# typewriter_shift.net
KiCad netlist of a schematic drawn in EAGLE
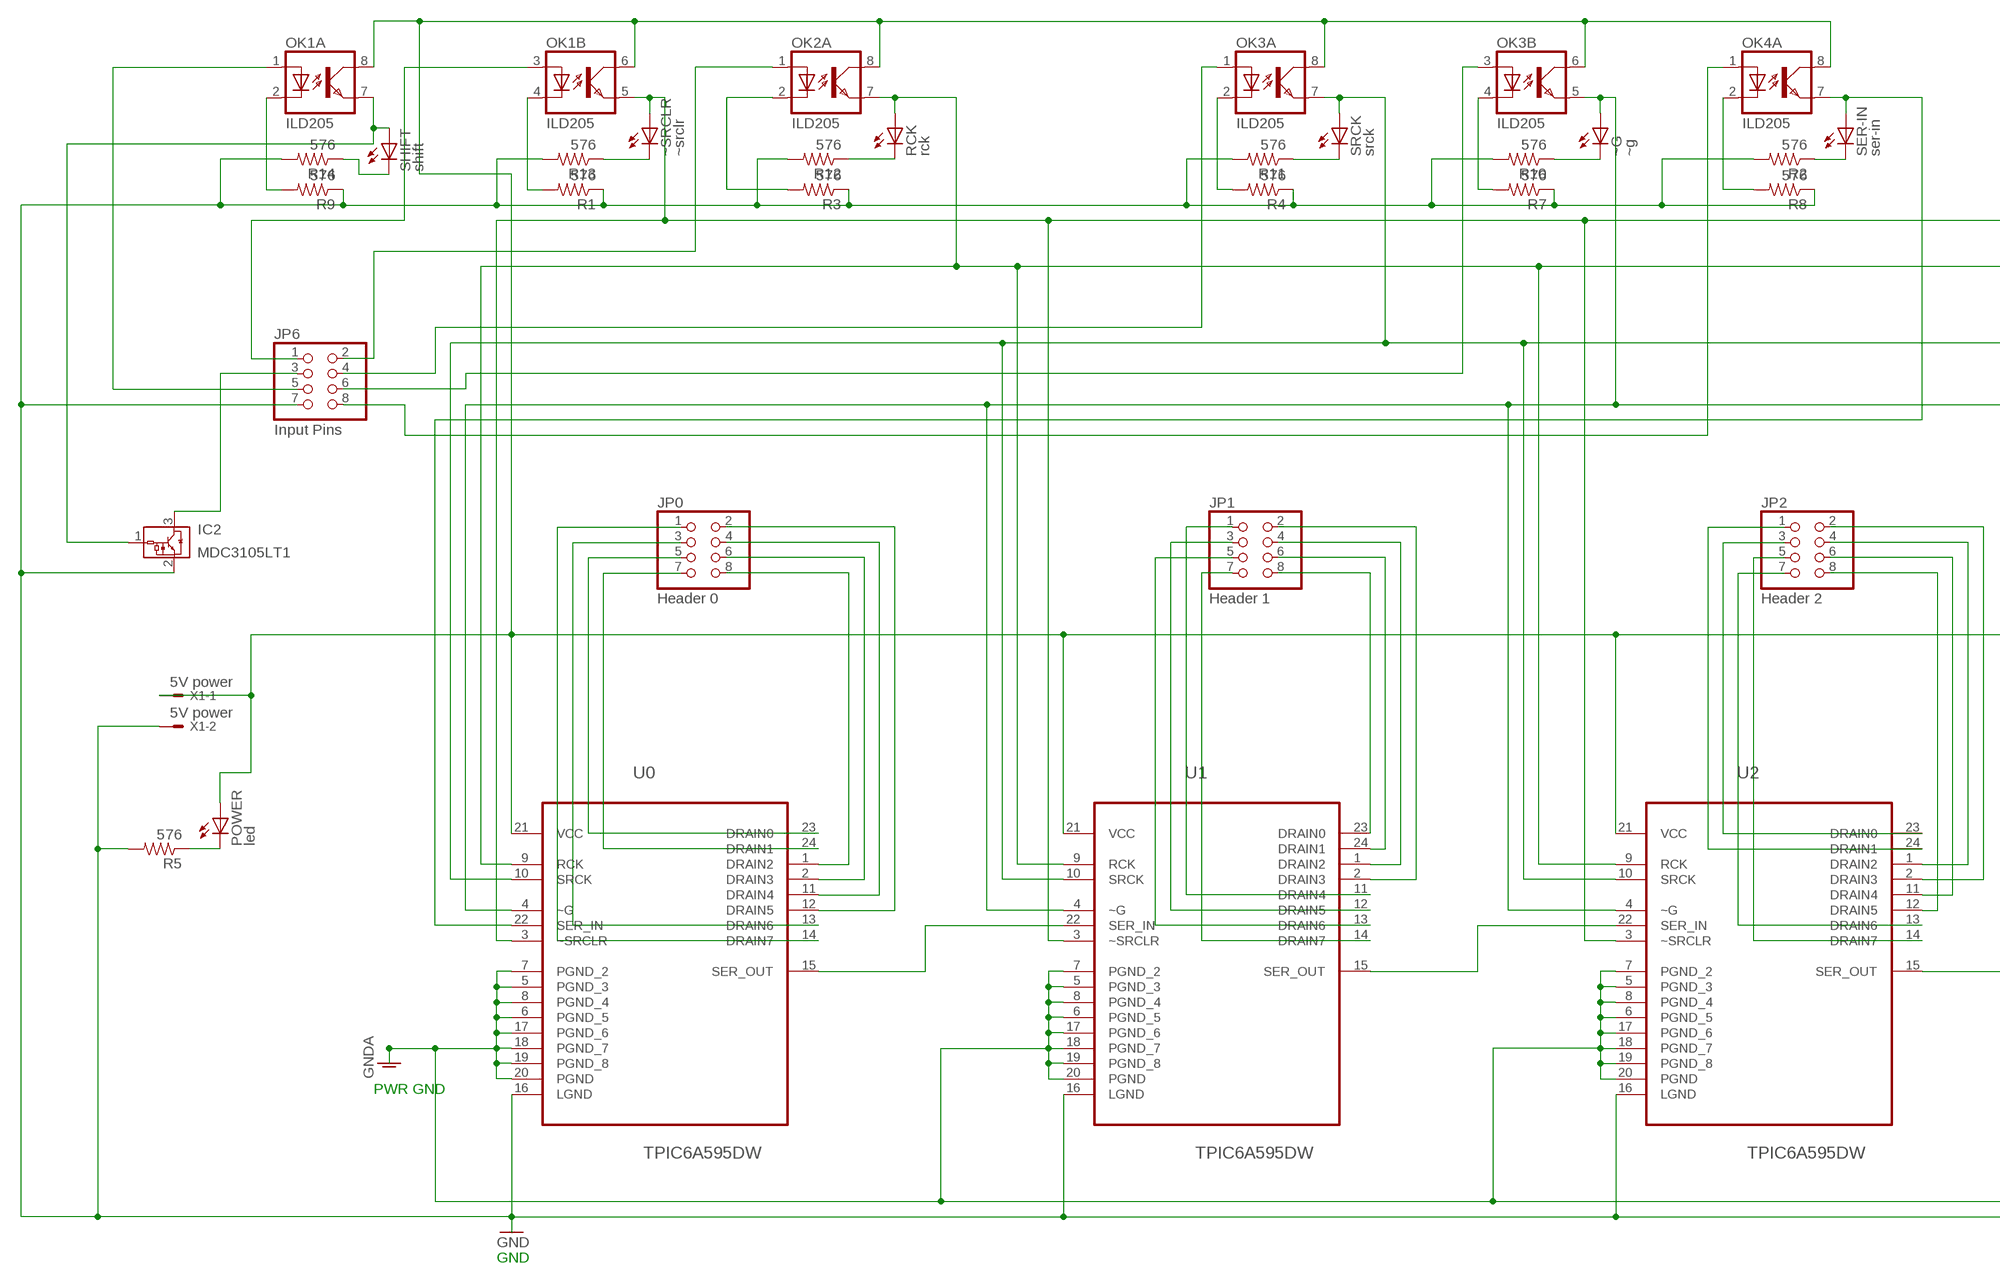
[diagram p0: schematic, sheet 1, part 1 of 2]
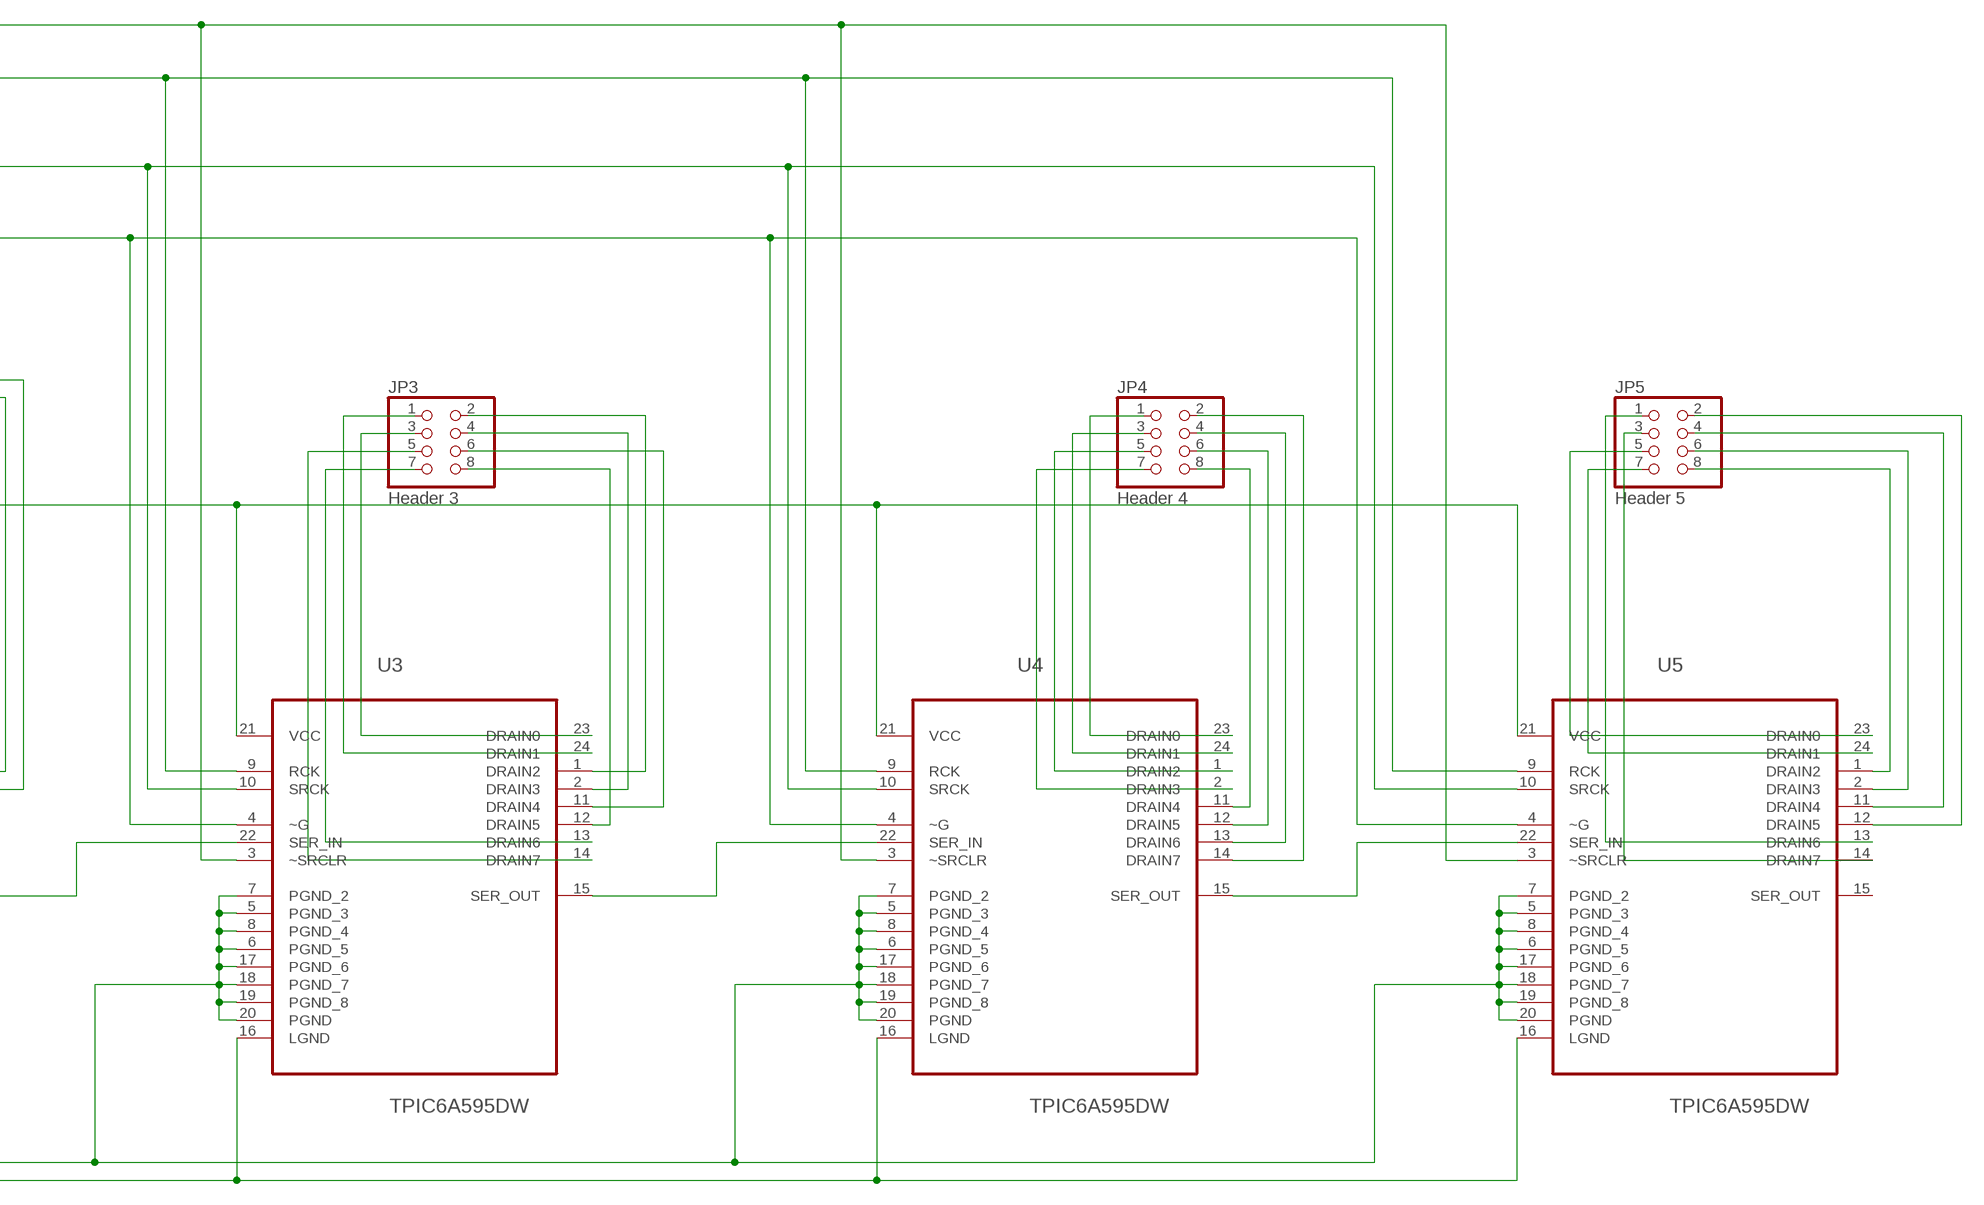
[diagram p1: schematic, sheet 1, part 2 of 2]

(export (version "E")
  (design (tool "Eeschema 10.0.6"))
  (components
    (comp (ref "IC2")
      (value "MDC3105LT1")
      (footprint "eagle-import:SOT23")
      (fields (field (name "MF") "ON SEMICONDUCTOR"))
      (libsource (lib "eagle-import") (part "MDC3105LT1"))
    )
    (comp (ref "JP0")
      (value "Header 0")
      (footprint "eagle-import:2X04_90")
      (libsource (lib "eagle-import") (part "PINHD-2X4/90"))
    )
    (comp (ref "JP1")
      (value "Header 1")
      (footprint "eagle-import:2X04_90")
      (libsource (lib "eagle-import") (part "PINHD-2X4/90"))
    )
    (comp (ref "JP2")
      (value "Header 2")
      (footprint "eagle-import:2X04_90")
      (libsource (lib "eagle-import") (part "PINHD-2X4/90"))
    )
    (comp (ref "JP3")
      (value "Header 3")
      (footprint "eagle-import:2X04_90")
      (libsource (lib "eagle-import") (part "PINHD-2X4/90"))
    )
    (comp (ref "JP4")
      (value "Header 4")
      (footprint "eagle-import:2X04_90")
      (libsource (lib "eagle-import") (part "PINHD-2X4/90"))
    )
    (comp (ref "JP5")
      (value "Header 5")
      (footprint "eagle-import:2X04_90")
      (libsource (lib "eagle-import") (part "PINHD-2X4/90"))
    )
    (comp (ref "JP6")
      (value "Input Pins")
      (footprint "eagle-import:2X04_90")
      (libsource (lib "eagle-import") (part "PINHD-2X4/90"))
    )
    (comp (ref "OK1")
      (value "ILD205")
      (footprint "eagle-import:SOIC08")
      (fields (field (name "MF") "VISHAY/TELEFUNKEN") (field (name "MPN") "ILD205T"))
      (libsource (lib "eagle-import") (part "ILD205"))
    )
    (comp (ref "OK2")
      (value "ILD205")
      (footprint "eagle-import:SOIC08")
      (fields (field (name "MF") "VISHAY/TELEFUNKEN") (field (name "MPN") "ILD205T"))
      (libsource (lib "eagle-import") (part "ILD205"))
    )
    (comp (ref "OK3")
      (value "ILD205")
      (footprint "eagle-import:SOIC08")
      (fields (field (name "MF") "VISHAY/TELEFUNKEN") (field (name "MPN") "ILD205T"))
      (libsource (lib "eagle-import") (part "ILD205"))
    )
    (comp (ref "OK4")
      (value "ILD205")
      (footprint "eagle-import:SOIC08")
      (fields (field (name "MF") "VISHAY/TELEFUNKEN") (field (name "MPN") "ILD205T"))
      (libsource (lib "eagle-import") (part "ILD205"))
    )
    (comp (ref "POWER")
      (value "led")
      (footprint "eagle-import:SML1206")
      (libsource (lib "eagle-import") (part "LEDSML1206"))
    )
    (comp (ref "R1")
      (value "576")
      (footprint "eagle-import:R2512")
      (libsource (lib "eagle-import") (part "R-US_R2512"))
    )
    (comp (ref "R2")
      (value "576")
      (footprint "eagle-import:R2512")
      (libsource (lib "eagle-import") (part "R-US_R2512"))
    )
    (comp (ref "R3")
      (value "576")
      (footprint "eagle-import:R2512")
      (libsource (lib "eagle-import") (part "R-US_R2512"))
    )
    (comp (ref "R4")
      (value "576")
      (footprint "eagle-import:R2512")
      (libsource (lib "eagle-import") (part "R-US_R2512"))
    )
    (comp (ref "R5")
      (value "576")
      (footprint "eagle-import:R2512")
      (libsource (lib "eagle-import") (part "R-US_R2512"))
    )
    (comp (ref "R7")
      (value "576")
      (footprint "eagle-import:R2512")
      (libsource (lib "eagle-import") (part "R-US_R2512"))
    )
    (comp (ref "R8")
      (value "576")
      (footprint "eagle-import:R2512")
      (libsource (lib "eagle-import") (part "R-US_R2512"))
    )
    (comp (ref "R9")
      (value "576")
      (footprint "eagle-import:R2512")
      (libsource (lib "eagle-import") (part "R-US_R2512"))
    )
    (comp (ref "R10")
      (value "576")
      (footprint "eagle-import:R2512")
      (libsource (lib "eagle-import") (part "R-US_R2512"))
    )
    (comp (ref "R11")
      (value "576")
      (footprint "eagle-import:R2512")
      (libsource (lib "eagle-import") (part "R-US_R2512"))
    )
    (comp (ref "R12")
      (value "576")
      (footprint "eagle-import:R2512")
      (libsource (lib "eagle-import") (part "R-US_R2512"))
    )
    (comp (ref "R13")
      (value "576")
      (footprint "eagle-import:R2512")
      (libsource (lib "eagle-import") (part "R-US_R2512"))
    )
    (comp (ref "R14")
      (value "576")
      (footprint "eagle-import:R2512")
      (libsource (lib "eagle-import") (part "R-US_R2512"))
    )
    (comp (ref "RCK")
      (value "rck")
      (footprint "eagle-import:SML1206")
      (libsource (lib "eagle-import") (part "LEDSML1206"))
    )
    (comp (ref "SER-IN")
      (value "ser-in")
      (footprint "eagle-import:SML1206")
      (libsource (lib "eagle-import") (part "LEDSML1206"))
    )
    (comp (ref "SHIFT")
      (value "shift")
      (footprint "eagle-import:SML1206")
      (libsource (lib "eagle-import") (part "LEDSML1206"))
    )
    (comp (ref "SRCK")
      (value "srck")
      (footprint "eagle-import:SML1206")
      (libsource (lib "eagle-import") (part "LEDSML1206"))
    )
    (comp (ref "U0")
      (value "TPIC6A595DW")
      (footprint "eagle-import:SOIC127P1030X265-24N")
      (libsource (lib "eagle-import") (part "TPIC6A595DW"))
    )
    (comp (ref "U1")
      (value "TPIC6A595DW")
      (footprint "eagle-import:SOIC127P1030X265-24N")
      (libsource (lib "eagle-import") (part "TPIC6A595DW"))
    )
    (comp (ref "U2")
      (value "TPIC6A595DW")
      (footprint "eagle-import:SOIC127P1030X265-24N")
      (libsource (lib "eagle-import") (part "TPIC6A595DW"))
    )
    (comp (ref "U3")
      (value "TPIC6A595DW")
      (footprint "eagle-import:SOIC127P1030X265-24N")
      (libsource (lib "eagle-import") (part "TPIC6A595DW"))
    )
    (comp (ref "U4")
      (value "TPIC6A595DW")
      (footprint "eagle-import:SOIC127P1030X265-24N")
      (libsource (lib "eagle-import") (part "TPIC6A595DW"))
    )
    (comp (ref "U5")
      (value "TPIC6A595DW")
      (footprint "eagle-import:SOIC127P1030X265-24N")
      (libsource (lib "eagle-import") (part "TPIC6A595DW"))
    )
    (comp (ref "X1")
      (value "5V power")
      (footprint "eagle-import:KK-156-2")
      (libsource (lib "eagle-import") (part "KK-156-2"))
    )
    (comp (ref "~G")
      (value "~g")
      (footprint "eagle-import:SML1206")
      (libsource (lib "eagle-import") (part "LEDSML1206"))
    )
    (comp (ref "~SRCLR")
      (value "~srclr")
      (footprint "eagle-import:SML1206")
      (libsource (lib "eagle-import") (part "LEDSML1206"))
    )
  )
  (nets
    (net (code "1") (name "GND") (class "Default")
      (node (ref "IC2") (pin "2") (pinfunction "GND_2") (pintype "passive"))
      (node (ref "JP6") (pin "7") (pinfunction "7_7") (pintype "passive"))
      (node (ref "R1") (pin "1") (pinfunction "1_1") (pintype "passive"))
      (node (ref "R10") (pin "2") (pinfunction "2_2") (pintype "passive"))
      (node (ref "R11") (pin "2") (pinfunction "2_2") (pintype "passive"))
      (node (ref "R12") (pin "2") (pinfunction "2_2") (pintype "passive"))
      (node (ref "R13") (pin "2") (pinfunction "2_2") (pintype "passive"))
      (node (ref "R14") (pin "2") (pinfunction "2_2") (pintype "passive"))
      (node (ref "R2") (pin "2") (pinfunction "2_2") (pintype "passive"))
      (node (ref "R3") (pin "1") (pinfunction "1_1") (pintype "passive"))
      (node (ref "R4") (pin "1") (pinfunction "1_1") (pintype "passive"))
      (node (ref "R5") (pin "2") (pinfunction "2_2") (pintype "passive"))
      (node (ref "R7") (pin "1") (pinfunction "1_1") (pintype "passive"))
      (node (ref "R8") (pin "1") (pinfunction "1_1") (pintype "passive"))
      (node (ref "R9") (pin "1") (pinfunction "1_1") (pintype "passive"))
      (node (ref "U0") (pin "16") (pinfunction "LGND_16") (pintype "passive"))
      (node (ref "U1") (pin "16") (pinfunction "LGND_16") (pintype "passive"))
      (node (ref "U2") (pin "16") (pinfunction "LGND_16") (pintype "passive"))
      (node (ref "U3") (pin "16") (pinfunction "LGND_16") (pintype "passive"))
      (node (ref "U4") (pin "16") (pinfunction "LGND_16") (pintype "passive"))
      (node (ref "U5") (pin "16") (pinfunction "LGND_16") (pintype "passive"))
      (node (ref "X1") (pin "2") (pinfunction "S_2") (pintype "passive"))
    )
    (net (code "2") (name "GNDA") (class "Default")
      (node (ref "U0") (pin "17") (pinfunction "PGND_6_17") (pintype "passive"))
      (node (ref "U0") (pin "18") (pinfunction "PGND_7_18") (pintype "passive"))
      (node (ref "U0") (pin "19") (pinfunction "PGND_8_19") (pintype "passive"))
      (node (ref "U0") (pin "20") (pinfunction "PGND_20") (pintype "passive"))
      (node (ref "U0") (pin "5") (pinfunction "PGND_3_5") (pintype "passive"))
      (node (ref "U0") (pin "6") (pinfunction "PGND_5_6") (pintype "passive"))
      (node (ref "U0") (pin "7") (pinfunction "PGND_2_7") (pintype "passive"))
      (node (ref "U0") (pin "8") (pinfunction "PGND_4_8") (pintype "passive"))
      (node (ref "U1") (pin "17") (pinfunction "PGND_6_17") (pintype "passive"))
      (node (ref "U1") (pin "18") (pinfunction "PGND_7_18") (pintype "passive"))
      (node (ref "U1") (pin "19") (pinfunction "PGND_8_19") (pintype "passive"))
      (node (ref "U1") (pin "20") (pinfunction "PGND_20") (pintype "passive"))
      (node (ref "U1") (pin "5") (pinfunction "PGND_3_5") (pintype "passive"))
      (node (ref "U1") (pin "6") (pinfunction "PGND_5_6") (pintype "passive"))
      (node (ref "U1") (pin "7") (pinfunction "PGND_2_7") (pintype "passive"))
      (node (ref "U1") (pin "8") (pinfunction "PGND_4_8") (pintype "passive"))
      (node (ref "U2") (pin "17") (pinfunction "PGND_6_17") (pintype "passive"))
      (node (ref "U2") (pin "18") (pinfunction "PGND_7_18") (pintype "passive"))
      (node (ref "U2") (pin "19") (pinfunction "PGND_8_19") (pintype "passive"))
      (node (ref "U2") (pin "20") (pinfunction "PGND_20") (pintype "passive"))
      (node (ref "U2") (pin "5") (pinfunction "PGND_3_5") (pintype "passive"))
      (node (ref "U2") (pin "6") (pinfunction "PGND_5_6") (pintype "passive"))
      (node (ref "U2") (pin "7") (pinfunction "PGND_2_7") (pintype "passive"))
      (node (ref "U2") (pin "8") (pinfunction "PGND_4_8") (pintype "passive"))
      (node (ref "U3") (pin "17") (pinfunction "PGND_6_17") (pintype "passive"))
      (node (ref "U3") (pin "18") (pinfunction "PGND_7_18") (pintype "passive"))
      (node (ref "U3") (pin "19") (pinfunction "PGND_8_19") (pintype "passive"))
      (node (ref "U3") (pin "20") (pinfunction "PGND_20") (pintype "passive"))
      (node (ref "U3") (pin "5") (pinfunction "PGND_3_5") (pintype "passive"))
      (node (ref "U3") (pin "6") (pinfunction "PGND_5_6") (pintype "passive"))
      (node (ref "U3") (pin "7") (pinfunction "PGND_2_7") (pintype "passive"))
      (node (ref "U3") (pin "8") (pinfunction "PGND_4_8") (pintype "passive"))
      (node (ref "U4") (pin "17") (pinfunction "PGND_6_17") (pintype "passive"))
      (node (ref "U4") (pin "18") (pinfunction "PGND_7_18") (pintype "passive"))
      (node (ref "U4") (pin "19") (pinfunction "PGND_8_19") (pintype "passive"))
      (node (ref "U4") (pin "20") (pinfunction "PGND_20") (pintype "passive"))
      (node (ref "U4") (pin "5") (pinfunction "PGND_3_5") (pintype "passive"))
      (node (ref "U4") (pin "6") (pinfunction "PGND_5_6") (pintype "passive"))
      (node (ref "U4") (pin "7") (pinfunction "PGND_2_7") (pintype "passive"))
      (node (ref "U4") (pin "8") (pinfunction "PGND_4_8") (pintype "passive"))
      (node (ref "U5") (pin "17") (pinfunction "PGND_6_17") (pintype "passive"))
      (node (ref "U5") (pin "18") (pinfunction "PGND_7_18") (pintype "passive"))
      (node (ref "U5") (pin "19") (pinfunction "PGND_8_19") (pintype "passive"))
      (node (ref "U5") (pin "20") (pinfunction "PGND_20") (pintype "passive"))
      (node (ref "U5") (pin "5") (pinfunction "PGND_3_5") (pintype "passive"))
      (node (ref "U5") (pin "6") (pinfunction "PGND_5_6") (pintype "passive"))
      (node (ref "U5") (pin "7") (pinfunction "PGND_2_7") (pintype "passive"))
      (node (ref "U5") (pin "8") (pinfunction "PGND_4_8") (pintype "passive"))
    )
    (net (code "3") (name "Net-(IC2-VIN)") (class "Default")
      (node (ref "IC2") (pin "1") (pinfunction "VIN_1") (pintype "passive"))
      (node (ref "OK1") (pin "7") (pinfunction "EMIT_7") (pintype "passive"))
      (node (ref "SHIFT") (pin "A") (pinfunction "A_A") (pintype "passive"))
    )
    (net (code "4") (name "Net-(IC2-VOUT)") (class "Default")
      (node (ref "IC2") (pin "3") (pinfunction "VOUT_3") (pintype "passive"))
      (node (ref "JP6") (pin "3") (pinfunction "3_3") (pintype "passive"))
    )
    (net (code "5") (name "Net-(OK1A-A)") (class "Default")
      (node (ref "JP6") (pin "5") (pinfunction "5_5") (pintype "passive"))
      (node (ref "OK1") (pin "1") (pinfunction "A_1") (pintype "passive"))
    )
    (net (code "6") (name "Net-(OK1A-C)") (class "Default")
      (node (ref "OK1") (pin "2") (pinfunction "C_2") (pintype "passive"))
      (node (ref "R9") (pin "2") (pinfunction "2_2") (pintype "passive"))
    )
    (net (code "7") (name "Net-(OK1A-COL)") (class "Default")
      (node (ref "OK1") (pin "6") (pinfunction "COL_6") (pintype "passive"))
      (node (ref "OK1") (pin "8") (pinfunction "COL_8") (pintype "passive"))
      (node (ref "OK2") (pin "8") (pinfunction "COL_8") (pintype "passive"))
      (node (ref "OK3") (pin "6") (pinfunction "COL_6") (pintype "passive"))
      (node (ref "OK3") (pin "8") (pinfunction "COL_8") (pintype "passive"))
      (node (ref "OK4") (pin "8") (pinfunction "COL_8") (pintype "passive"))
      (node (ref "POWER") (pin "A") (pinfunction "A_A") (pintype "passive"))
      (node (ref "U0") (pin "21") (pinfunction "VCC_21") (pintype "power_in"))
      (node (ref "U1") (pin "21") (pinfunction "VCC_21") (pintype "power_in"))
      (node (ref "U2") (pin "21") (pinfunction "VCC_21") (pintype "power_in"))
      (node (ref "U3") (pin "21") (pinfunction "VCC_21") (pintype "power_in"))
      (node (ref "U4") (pin "21") (pinfunction "VCC_21") (pintype "power_in"))
      (node (ref "U5") (pin "21") (pinfunction "VCC_21") (pintype "power_in"))
      (node (ref "X1") (pin "1") (pinfunction "S_1") (pintype "passive"))
    )
    (net (code "8") (name "Net-(OK1B-A)") (class "Default")
      (node (ref "JP6") (pin "1") (pinfunction "1_1") (pintype "passive"))
      (node (ref "OK1") (pin "3") (pinfunction "A_3") (pintype "passive"))
    )
    (net (code "9") (name "Net-(OK1B-C)") (class "Default")
      (node (ref "OK1") (pin "4") (pinfunction "C_4") (pintype "passive"))
      (node (ref "R1") (pin "2") (pinfunction "2_2") (pintype "passive"))
    )
    (net (code "10") (name "Net-(OK1B-EMIT)") (class "Default")
      (node (ref "OK1") (pin "5") (pinfunction "EMIT_5") (pintype "passive"))
      (node (ref "U0") (pin "3") (pinfunction "~{SRCLR}_3") (pintype "input"))
      (node (ref "U1") (pin "3") (pinfunction "~{SRCLR}_3") (pintype "input"))
      (node (ref "U2") (pin "3") (pinfunction "~{SRCLR}_3") (pintype "input"))
      (node (ref "U3") (pin "3") (pinfunction "~{SRCLR}_3") (pintype "input"))
      (node (ref "U4") (pin "3") (pinfunction "~{SRCLR}_3") (pintype "input"))
      (node (ref "U5") (pin "3") (pinfunction "~{SRCLR}_3") (pintype "input"))
      (node (ref "~SRCLR") (pin "A") (pinfunction "A_A") (pintype "passive"))
    )
    (net (code "11") (name "Net-(OK2A-A)") (class "Default")
      (node (ref "JP6") (pin "2") (pinfunction "2_2") (pintype "passive"))
      (node (ref "OK2") (pin "1") (pinfunction "A_1") (pintype "passive"))
    )
    (net (code "12") (name "Net-(OK2A-C)") (class "Default")
      (node (ref "OK2") (pin "2") (pinfunction "C_2") (pintype "passive"))
      (node (ref "R3") (pin "2") (pinfunction "2_2") (pintype "passive"))
    )
    (net (code "13") (name "Net-(OK2A-EMIT)") (class "Default")
      (node (ref "OK2") (pin "7") (pinfunction "EMIT_7") (pintype "passive"))
      (node (ref "RCK") (pin "A") (pinfunction "A_A") (pintype "passive"))
      (node (ref "U0") (pin "9") (pinfunction "RCK_9") (pintype "input"))
      (node (ref "U1") (pin "9") (pinfunction "RCK_9") (pintype "input"))
      (node (ref "U2") (pin "9") (pinfunction "RCK_9") (pintype "input"))
      (node (ref "U3") (pin "9") (pinfunction "RCK_9") (pintype "input"))
      (node (ref "U4") (pin "9") (pinfunction "RCK_9") (pintype "input"))
      (node (ref "U5") (pin "9") (pinfunction "RCK_9") (pintype "input"))
    )
    (net (code "14") (name "Net-(OK3A-A)") (class "Default")
      (node (ref "JP6") (pin "4") (pinfunction "4_4") (pintype "passive"))
      (node (ref "OK3") (pin "1") (pinfunction "A_1") (pintype "passive"))
    )
    (net (code "15") (name "Net-(OK3A-C)") (class "Default")
      (node (ref "OK3") (pin "2") (pinfunction "C_2") (pintype "passive"))
      (node (ref "R4") (pin "2") (pinfunction "2_2") (pintype "passive"))
    )
    (net (code "16") (name "Net-(OK3A-EMIT)") (class "Default")
      (node (ref "OK3") (pin "7") (pinfunction "EMIT_7") (pintype "passive"))
      (node (ref "SRCK") (pin "A") (pinfunction "A_A") (pintype "passive"))
      (node (ref "U0") (pin "10") (pinfunction "SRCK_10") (pintype "input"))
      (node (ref "U1") (pin "10") (pinfunction "SRCK_10") (pintype "input"))
      (node (ref "U2") (pin "10") (pinfunction "SRCK_10") (pintype "input"))
      (node (ref "U3") (pin "10") (pinfunction "SRCK_10") (pintype "input"))
      (node (ref "U4") (pin "10") (pinfunction "SRCK_10") (pintype "input"))
      (node (ref "U5") (pin "10") (pinfunction "SRCK_10") (pintype "input"))
    )
    (net (code "17") (name "Net-(OK3B-A)") (class "Default")
      (node (ref "JP6") (pin "6") (pinfunction "6_6") (pintype "passive"))
      (node (ref "OK3") (pin "3") (pinfunction "A_3") (pintype "passive"))
    )
    (net (code "18") (name "Net-(OK3B-C)") (class "Default")
      (node (ref "OK3") (pin "4") (pinfunction "C_4") (pintype "passive"))
      (node (ref "R7") (pin "2") (pinfunction "2_2") (pintype "passive"))
    )
    (net (code "19") (name "Net-(OK3B-EMIT)") (class "Default")
      (node (ref "OK3") (pin "5") (pinfunction "EMIT_5") (pintype "passive"))
      (node (ref "U0") (pin "4") (pinfunction "~{G}_4") (pintype "input"))
      (node (ref "U1") (pin "4") (pinfunction "~{G}_4") (pintype "input"))
      (node (ref "U2") (pin "4") (pinfunction "~{G}_4") (pintype "input"))
      (node (ref "U3") (pin "4") (pinfunction "~{G}_4") (pintype "input"))
      (node (ref "U4") (pin "4") (pinfunction "~{G}_4") (pintype "input"))
      (node (ref "U5") (pin "4") (pinfunction "~{G}_4") (pintype "input"))
      (node (ref "~G") (pin "A") (pinfunction "A_A") (pintype "passive"))
    )
    (net (code "20") (name "Net-(OK4A-A)") (class "Default")
      (node (ref "JP6") (pin "8") (pinfunction "8_8") (pintype "passive"))
      (node (ref "OK4") (pin "1") (pinfunction "A_1") (pintype "passive"))
    )
    (net (code "21") (name "Net-(OK4A-C)") (class "Default")
      (node (ref "OK4") (pin "2") (pinfunction "C_2") (pintype "passive"))
      (node (ref "R8") (pin "2") (pinfunction "2_2") (pintype "passive"))
    )
    (net (code "22") (name "Net-(OK4A-EMIT)") (class "Default")
      (node (ref "OK4") (pin "7") (pinfunction "EMIT_7") (pintype "passive"))
      (node (ref "SER-IN") (pin "A") (pinfunction "A_A") (pintype "passive"))
      (node (ref "U0") (pin "22") (pinfunction "SER_IN_22") (pintype "input"))
    )
    (net (code "23") (name "Net-(POWER-PadC)") (class "Default")
      (node (ref "POWER") (pin "C") (pinfunction "C_C") (pintype "passive"))
      (node (ref "R5") (pin "1") (pinfunction "1_1") (pintype "passive"))
    )
    (net (code "24") (name "Net-(R2-Pad1)") (class "Default")
      (node (ref "R2") (pin "1") (pinfunction "1_1") (pintype "passive"))
      (node (ref "SER-IN") (pin "C") (pinfunction "C_C") (pintype "passive"))
    )
    (net (code "25") (name "Net-(R10-Pad1)") (class "Default")
      (node (ref "R10") (pin "1") (pinfunction "1_1") (pintype "passive"))
      (node (ref "~G") (pin "C") (pinfunction "C_C") (pintype "passive"))
    )
    (net (code "26") (name "Net-(R11-Pad1)") (class "Default")
      (node (ref "R11") (pin "1") (pinfunction "1_1") (pintype "passive"))
      (node (ref "SRCK") (pin "C") (pinfunction "C_C") (pintype "passive"))
    )
    (net (code "27") (name "Net-(R12-Pad1)") (class "Default")
      (node (ref "R12") (pin "1") (pinfunction "1_1") (pintype "passive"))
      (node (ref "RCK") (pin "C") (pinfunction "C_C") (pintype "passive"))
    )
    (net (code "28") (name "Net-(R13-Pad1)") (class "Default")
      (node (ref "R13") (pin "1") (pinfunction "1_1") (pintype "passive"))
      (node (ref "~SRCLR") (pin "C") (pinfunction "C_C") (pintype "passive"))
    )
    (net (code "29") (name "Net-(R14-Pad1)") (class "Default")
      (node (ref "R14") (pin "1") (pinfunction "1_1") (pintype "passive"))
      (node (ref "SHIFT") (pin "C") (pinfunction "C_C") (pintype "passive"))
    )
    (net (code "30") (name "Net-(U0-DRAIN0)") (class "Default")
      (node (ref "JP0") (pin "5") (pinfunction "5_5") (pintype "passive"))
      (node (ref "U0") (pin "23") (pinfunction "DRAIN0_23") (pintype "output"))
    )
    (net (code "31") (name "Net-(U0-DRAIN1)") (class "Default")
      (node (ref "JP0") (pin "7") (pinfunction "7_7") (pintype "passive"))
      (node (ref "U0") (pin "24") (pinfunction "DRAIN1_24") (pintype "output"))
    )
    (net (code "32") (name "Net-(U0-DRAIN2)") (class "Default")
      (node (ref "JP0") (pin "8") (pinfunction "8_8") (pintype "passive"))
      (node (ref "U0") (pin "1") (pinfunction "DRAIN2_1") (pintype "output"))
    )
    (net (code "33") (name "Net-(U0-DRAIN3)") (class "Default")
      (node (ref "JP0") (pin "6") (pinfunction "6_6") (pintype "passive"))
      (node (ref "U0") (pin "2") (pinfunction "DRAIN3_2") (pintype "output"))
    )
    (net (code "34") (name "Net-(U0-DRAIN4)") (class "Default")
      (node (ref "JP0") (pin "4") (pinfunction "4_4") (pintype "passive"))
      (node (ref "U0") (pin "11") (pinfunction "DRAIN4_11") (pintype "output"))
    )
    (net (code "35") (name "Net-(U0-DRAIN5)") (class "Default")
      (node (ref "JP0") (pin "2") (pinfunction "2_2") (pintype "passive"))
      (node (ref "U0") (pin "12") (pinfunction "DRAIN5_12") (pintype "output"))
    )
    (net (code "36") (name "Net-(U0-DRAIN6)") (class "Default")
      (node (ref "JP0") (pin "3") (pinfunction "3_3") (pintype "passive"))
      (node (ref "U0") (pin "13") (pinfunction "DRAIN6_13") (pintype "output"))
    )
    (net (code "37") (name "Net-(U0-DRAIN7)") (class "Default")
      (node (ref "JP0") (pin "1") (pinfunction "1_1") (pintype "passive"))
      (node (ref "U0") (pin "14") (pinfunction "DRAIN7_14") (pintype "output"))
    )
    (net (code "38") (name "Net-(U0-SER_OUT)") (class "Default")
      (node (ref "U0") (pin "15") (pinfunction "SER_OUT_15") (pintype "output"))
      (node (ref "U1") (pin "22") (pinfunction "SER_IN_22") (pintype "input"))
    )
    (net (code "39") (name "Net-(U1-DRAIN0)") (class "Default")
      (node (ref "JP1") (pin "8") (pinfunction "8_8") (pintype "passive"))
      (node (ref "U1") (pin "23") (pinfunction "DRAIN0_23") (pintype "output"))
    )
    (net (code "40") (name "Net-(U1-DRAIN1)") (class "Default")
      (node (ref "JP1") (pin "6") (pinfunction "6_6") (pintype "passive"))
      (node (ref "U1") (pin "24") (pinfunction "DRAIN1_24") (pintype "output"))
    )
    (net (code "41") (name "Net-(U1-DRAIN2)") (class "Default")
      (node (ref "JP1") (pin "4") (pinfunction "4_4") (pintype "passive"))
      (node (ref "U1") (pin "1") (pinfunction "DRAIN2_1") (pintype "output"))
    )
    (net (code "42") (name "Net-(U1-DRAIN3)") (class "Default")
      (node (ref "JP1") (pin "2") (pinfunction "2_2") (pintype "passive"))
      (node (ref "U1") (pin "2") (pinfunction "DRAIN3_2") (pintype "output"))
    )
    (net (code "43") (name "Net-(U1-DRAIN4)") (class "Default")
      (node (ref "JP1") (pin "1") (pinfunction "1_1") (pintype "passive"))
      (node (ref "U1") (pin "11") (pinfunction "DRAIN4_11") (pintype "output"))
    )
    (net (code "44") (name "Net-(U1-DRAIN5)") (class "Default")
      (node (ref "JP1") (pin "3") (pinfunction "3_3") (pintype "passive"))
      (node (ref "U1") (pin "12") (pinfunction "DRAIN5_12") (pintype "output"))
    )
    (net (code "45") (name "Net-(U1-DRAIN6)") (class "Default")
      (node (ref "JP1") (pin "5") (pinfunction "5_5") (pintype "passive"))
      (node (ref "U1") (pin "13") (pinfunction "DRAIN6_13") (pintype "output"))
    )
    (net (code "46") (name "Net-(U1-DRAIN7)") (class "Default")
      (node (ref "JP1") (pin "7") (pinfunction "7_7") (pintype "passive"))
      (node (ref "U1") (pin "14") (pinfunction "DRAIN7_14") (pintype "output"))
    )
    (net (code "47") (name "Net-(U1-SER_OUT)") (class "Default")
      (node (ref "U1") (pin "15") (pinfunction "SER_OUT_15") (pintype "output"))
      (node (ref "U2") (pin "22") (pinfunction "SER_IN_22") (pintype "input"))
    )
    (net (code "48") (name "Net-(U2-DRAIN0)") (class "Default")
      (node (ref "JP2") (pin "3") (pinfunction "3_3") (pintype "passive"))
      (node (ref "U2") (pin "23") (pinfunction "DRAIN0_23") (pintype "output"))
    )
    (net (code "49") (name "Net-(U2-DRAIN1)") (class "Default")
      (node (ref "JP2") (pin "1") (pinfunction "1_1") (pintype "passive"))
      (node (ref "U2") (pin "24") (pinfunction "DRAIN1_24") (pintype "output"))
    )
    (net (code "50") (name "Net-(U2-DRAIN2)") (class "Default")
      (node (ref "JP2") (pin "4") (pinfunction "4_4") (pintype "passive"))
      (node (ref "U2") (pin "1") (pinfunction "DRAIN2_1") (pintype "output"))
    )
    (net (code "51") (name "Net-(U2-DRAIN3)") (class "Default")
      (node (ref "JP2") (pin "2") (pinfunction "2_2") (pintype "passive"))
      (node (ref "U2") (pin "2") (pinfunction "DRAIN3_2") (pintype "output"))
    )
    (net (code "52") (name "Net-(U2-DRAIN4)") (class "Default")
      (node (ref "JP2") (pin "6") (pinfunction "6_6") (pintype "passive"))
      (node (ref "U2") (pin "11") (pinfunction "DRAIN4_11") (pintype "output"))
    )
    (net (code "53") (name "Net-(U2-DRAIN5)") (class "Default")
      (node (ref "JP2") (pin "8") (pinfunction "8_8") (pintype "passive"))
      (node (ref "U2") (pin "12") (pinfunction "DRAIN5_12") (pintype "output"))
    )
    (net (code "54") (name "Net-(U2-DRAIN6)") (class "Default")
      (node (ref "JP2") (pin "7") (pinfunction "7_7") (pintype "passive"))
      (node (ref "U2") (pin "13") (pinfunction "DRAIN6_13") (pintype "output"))
    )
    (net (code "55") (name "Net-(U2-DRAIN7)") (class "Default")
      (node (ref "JP2") (pin "5") (pinfunction "5_5") (pintype "passive"))
      (node (ref "U2") (pin "14") (pinfunction "DRAIN7_14") (pintype "output"))
    )
    (net (code "56") (name "Net-(U2-SER_OUT)") (class "Default")
      (node (ref "U2") (pin "15") (pinfunction "SER_OUT_15") (pintype "output"))
      (node (ref "U3") (pin "22") (pinfunction "SER_IN_22") (pintype "input"))
    )
    (net (code "57") (name "Net-(U3-DRAIN0)") (class "Default")
      (node (ref "JP3") (pin "3") (pinfunction "3_3") (pintype "passive"))
      (node (ref "U3") (pin "23") (pinfunction "DRAIN0_23") (pintype "output"))
    )
    (net (code "58") (name "Net-(U3-DRAIN1)") (class "Default")
      (node (ref "JP3") (pin "1") (pinfunction "1_1") (pintype "passive"))
      (node (ref "U3") (pin "24") (pinfunction "DRAIN1_24") (pintype "output"))
    )
    (net (code "59") (name "Net-(U3-DRAIN2)") (class "Default")
      (node (ref "JP3") (pin "2") (pinfunction "2_2") (pintype "passive"))
      (node (ref "U3") (pin "1") (pinfunction "DRAIN2_1") (pintype "output"))
    )
    (net (code "60") (name "Net-(U3-DRAIN3)") (class "Default")
      (node (ref "JP3") (pin "4") (pinfunction "4_4") (pintype "passive"))
      (node (ref "U3") (pin "2") (pinfunction "DRAIN3_2") (pintype "output"))
    )
    (net (code "61") (name "Net-(U3-DRAIN4)") (class "Default")
      (node (ref "JP3") (pin "6") (pinfunction "6_6") (pintype "passive"))
      (node (ref "U3") (pin "11") (pinfunction "DRAIN4_11") (pintype "output"))
    )
    (net (code "62") (name "Net-(U3-DRAIN5)") (class "Default")
      (node (ref "JP3") (pin "8") (pinfunction "8_8") (pintype "passive"))
      (node (ref "U3") (pin "12") (pinfunction "DRAIN5_12") (pintype "output"))
    )
    (net (code "63") (name "Net-(U3-DRAIN6)") (class "Default")
      (node (ref "JP3") (pin "7") (pinfunction "7_7") (pintype "passive"))
      (node (ref "U3") (pin "13") (pinfunction "DRAIN6_13") (pintype "output"))
    )
    (net (code "64") (name "Net-(U3-DRAIN7)") (class "Default")
      (node (ref "JP3") (pin "5") (pinfunction "5_5") (pintype "passive"))
      (node (ref "U3") (pin "14") (pinfunction "DRAIN7_14") (pintype "output"))
    )
    (net (code "65") (name "Net-(U3-SER_OUT)") (class "Default")
      (node (ref "U3") (pin "15") (pinfunction "SER_OUT_15") (pintype "output"))
      (node (ref "U4") (pin "22") (pinfunction "SER_IN_22") (pintype "input"))
    )
    (net (code "66") (name "Net-(U4-DRAIN0)") (class "Default")
      (node (ref "JP4") (pin "1") (pinfunction "1_1") (pintype "passive"))
      (node (ref "U4") (pin "23") (pinfunction "DRAIN0_23") (pintype "output"))
    )
    (net (code "67") (name "Net-(U4-DRAIN1)") (class "Default")
      (node (ref "JP4") (pin "3") (pinfunction "3_3") (pintype "passive"))
      (node (ref "U4") (pin "24") (pinfunction "DRAIN1_24") (pintype "output"))
    )
    (net (code "68") (name "Net-(U4-DRAIN2)") (class "Default")
      (node (ref "JP4") (pin "5") (pinfunction "5_5") (pintype "passive"))
      (node (ref "U4") (pin "1") (pinfunction "DRAIN2_1") (pintype "output"))
    )
    (net (code "69") (name "Net-(U4-DRAIN3)") (class "Default")
      (node (ref "JP4") (pin "7") (pinfunction "7_7") (pintype "passive"))
      (node (ref "U4") (pin "2") (pinfunction "DRAIN3_2") (pintype "output"))
    )
    (net (code "70") (name "Net-(U4-DRAIN4)") (class "Default")
      (node (ref "JP4") (pin "8") (pinfunction "8_8") (pintype "passive"))
      (node (ref "U4") (pin "11") (pinfunction "DRAIN4_11") (pintype "output"))
    )
    (net (code "71") (name "Net-(U4-DRAIN5)") (class "Default")
      (node (ref "JP4") (pin "6") (pinfunction "6_6") (pintype "passive"))
      (node (ref "U4") (pin "12") (pinfunction "DRAIN5_12") (pintype "output"))
    )
    (net (code "72") (name "Net-(U4-DRAIN6)") (class "Default")
      (node (ref "JP4") (pin "4") (pinfunction "4_4") (pintype "passive"))
      (node (ref "U4") (pin "13") (pinfunction "DRAIN6_13") (pintype "output"))
    )
    (net (code "73") (name "Net-(U4-DRAIN7)") (class "Default")
      (node (ref "JP4") (pin "2") (pinfunction "2_2") (pintype "passive"))
      (node (ref "U4") (pin "14") (pinfunction "DRAIN7_14") (pintype "output"))
    )
    (net (code "74") (name "Net-(U4-SER_OUT)") (class "Default")
      (node (ref "U4") (pin "15") (pinfunction "SER_OUT_15") (pintype "output"))
      (node (ref "U5") (pin "22") (pinfunction "SER_IN_22") (pintype "input"))
    )
    (net (code "75") (name "Net-(U5-DRAIN0)") (class "Default")
      (node (ref "JP5") (pin "5") (pinfunction "5_5") (pintype "passive"))
      (node (ref "U5") (pin "23") (pinfunction "DRAIN0_23") (pintype "output"))
    )
    (net (code "76") (name "Net-(U5-DRAIN1)") (class "Default")
      (node (ref "JP5") (pin "7") (pinfunction "7_7") (pintype "passive"))
      (node (ref "U5") (pin "24") (pinfunction "DRAIN1_24") (pintype "output"))
    )
    (net (code "77") (name "Net-(U5-DRAIN2)") (class "Default")
      (node (ref "JP5") (pin "8") (pinfunction "8_8") (pintype "passive"))
      (node (ref "U5") (pin "1") (pinfunction "DRAIN2_1") (pintype "output"))
    )
    (net (code "78") (name "Net-(U5-DRAIN3)") (class "Default")
      (node (ref "JP5") (pin "6") (pinfunction "6_6") (pintype "passive"))
      (node (ref "U5") (pin "2") (pinfunction "DRAIN3_2") (pintype "output"))
    )
    (net (code "79") (name "Net-(U5-DRAIN4)") (class "Default")
      (node (ref "JP5") (pin "4") (pinfunction "4_4") (pintype "passive"))
      (node (ref "U5") (pin "11") (pinfunction "DRAIN4_11") (pintype "output"))
    )
    (net (code "80") (name "Net-(U5-DRAIN5)") (class "Default")
      (node (ref "JP5") (pin "2") (pinfunction "2_2") (pintype "passive"))
      (node (ref "U5") (pin "12") (pinfunction "DRAIN5_12") (pintype "output"))
    )
    (net (code "81") (name "Net-(U5-DRAIN6)") (class "Default")
      (node (ref "JP5") (pin "1") (pinfunction "1_1") (pintype "passive"))
      (node (ref "U5") (pin "13") (pinfunction "DRAIN6_13") (pintype "output"))
    )
    (net (code "82") (name "Net-(U5-DRAIN7)") (class "Default")
      (node (ref "JP5") (pin "3") (pinfunction "3_3") (pintype "passive"))
      (node (ref "U5") (pin "14") (pinfunction "DRAIN7_14") (pintype "output"))
    )
    (net (code "83") (name "unconnected-(U5-SER_OUT-Pad15)") (class "Default")
      (node (ref "U5") (pin "15") (pinfunction "SER_OUT_15") (pintype "output"))
    )
  )
)
